# HVSchematic.net
KiCad netlist of a schematic drawn in Altium Designer
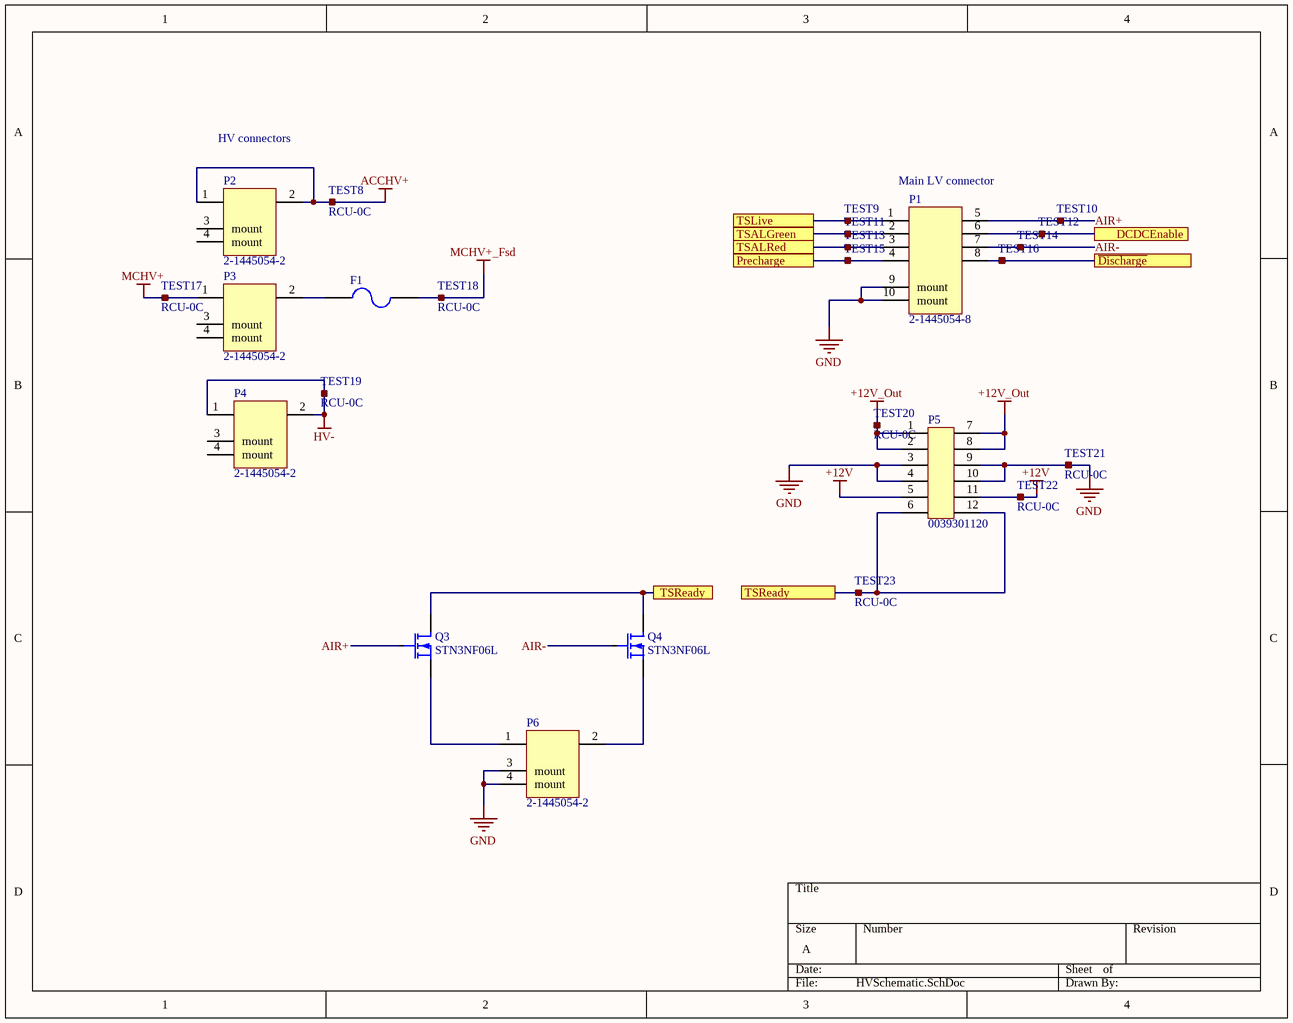
[diagram p0: HVSchematic.SchDoc]

(export (version "E")
  (design (tool "Eeschema 10.0.6"))
  (components
    (comp (ref "F1")
      (value "~")
      (footprint "0885004.DR")
      (fields (field (name "MFRPARTNO") "0885004.DR") (field (name "CREATED_BY") "Graydon"))
      (libsource (lib "Altium-Lib") (part "Fuse"))
    )
    (comp (ref "P1")
      (value "2-1445054-8")
      (footprint "2-1445054-8")
      (description "1x8 connector")
      (fields (field (name "CREATED_BY") "Graydon"))
      (libsource (lib "Altium-Lib") (part "2-1445054-8"))
    )
    (comp (ref "P2")
      (value "2-1445054-2")
      (footprint "2-1445054-2")
      (description "1x2 connector")
      (fields (field (name "CREATED_BY") "Graydon") (field (name "UPDATED_BY") "Null"))
      (libsource (lib "Altium-Lib") (part "2-1445054-2"))
    )
    (comp (ref "P3")
      (value "2-1445054-2")
      (footprint "2-1445054-2")
      (description "1x2 connector")
      (fields (field (name "CREATED_BY") "Graydon") (field (name "UPDATED_BY") "Null"))
      (libsource (lib "Altium-Lib") (part "2-1445054-2"))
    )
    (comp (ref "P4")
      (value "2-1445054-2")
      (footprint "2-1445054-2")
      (description "1x2 connector")
      (fields (field (name "CREATED_BY") "Graydon") (field (name "UPDATED_BY") "Null"))
      (libsource (lib "Altium-Lib") (part "2-1445054-2"))
    )
    (comp (ref "P5")
      (value "0039301120")
      (footprint "0039301120")
      (description "Molex Minifit Jr 12p right angle")
      (libsource (lib "Altium-Lib") (part "0039301120"))
    )
    (comp (ref "P6")
      (value "2-1445054-2")
      (footprint "2-1445054-2")
      (description "1x2 connector")
      (fields (field (name "CREATED_BY") "Graydon") (field (name "UPDATED_BY") "Null"))
      (libsource (lib "Altium-Lib") (part "2-1445054-2"))
    )
    (comp (ref "Q3")
      (value "STN3NF06L")
      (footprint "STN3NF06L")
      (description "MOSFET N-CH 60V 4A SOT223")
      (fields (field (name "CREATED_BY") "Graydon"))
      (libsource (lib "Altium-Lib") (part "STN3NF06L"))
    )
    (comp (ref "Q4")
      (value "STN3NF06L")
      (footprint "STN3NF06L")
      (description "MOSFET N-CH 60V 4A SOT223")
      (fields (field (name "CREATED_BY") "Graydon"))
      (libsource (lib "Altium-Lib") (part "STN3NF06L"))
    )
    (comp (ref "TEST8")
      (value "RCU-0C")
      (footprint "RCU-0C")
      (description "Test point")
      (fields (field (name "CREATED_BY") "Graydon") (field (name "UPDATED_BY") "Null"))
      (libsource (lib "Altium-Lib") (part "RCU-0C"))
    )
    (comp (ref "TEST9")
      (value "RCU-0C")
      (footprint "RCU-0C")
      (description "Test point")
      (fields (field (name "CREATED_BY") "Graydon") (field (name "UPDATED_BY") "Null"))
      (libsource (lib "Altium-Lib") (part "RCU-0C"))
    )
    (comp (ref "TEST10")
      (value "RCU-0C")
      (footprint "RCU-0C")
      (description "Test point")
      (fields (field (name "CREATED_BY") "Graydon") (field (name "UPDATED_BY") "Null"))
      (libsource (lib "Altium-Lib") (part "RCU-0C"))
    )
    (comp (ref "TEST11")
      (value "RCU-0C")
      (footprint "RCU-0C")
      (description "Test point")
      (fields (field (name "CREATED_BY") "Graydon") (field (name "UPDATED_BY") "Null"))
      (libsource (lib "Altium-Lib") (part "RCU-0C"))
    )
    (comp (ref "TEST12")
      (value "RCU-0C")
      (footprint "RCU-0C")
      (description "Test point")
      (fields (field (name "CREATED_BY") "Graydon") (field (name "UPDATED_BY") "Null"))
      (libsource (lib "Altium-Lib") (part "RCU-0C"))
    )
    (comp (ref "TEST13")
      (value "RCU-0C")
      (footprint "RCU-0C")
      (description "Test point")
      (fields (field (name "CREATED_BY") "Graydon") (field (name "UPDATED_BY") "Null"))
      (libsource (lib "Altium-Lib") (part "RCU-0C"))
    )
    (comp (ref "TEST14")
      (value "RCU-0C")
      (footprint "RCU-0C")
      (description "Test point")
      (fields (field (name "CREATED_BY") "Graydon") (field (name "UPDATED_BY") "Null"))
      (libsource (lib "Altium-Lib") (part "RCU-0C"))
    )
    (comp (ref "TEST15")
      (value "RCU-0C")
      (footprint "RCU-0C")
      (description "Test point")
      (fields (field (name "CREATED_BY") "Graydon") (field (name "UPDATED_BY") "Null"))
      (libsource (lib "Altium-Lib") (part "RCU-0C"))
    )
    (comp (ref "TEST16")
      (value "RCU-0C")
      (footprint "RCU-0C")
      (description "Test point")
      (fields (field (name "CREATED_BY") "Graydon") (field (name "UPDATED_BY") "Null"))
      (libsource (lib "Altium-Lib") (part "RCU-0C"))
    )
    (comp (ref "TEST17")
      (value "RCU-0C")
      (footprint "RCU-0C")
      (description "Test point")
      (fields (field (name "CREATED_BY") "Graydon") (field (name "UPDATED_BY") "Null"))
      (libsource (lib "Altium-Lib") (part "RCU-0C"))
    )
    (comp (ref "TEST18")
      (value "RCU-0C")
      (footprint "RCU-0C")
      (description "Test point")
      (fields (field (name "CREATED_BY") "Graydon") (field (name "UPDATED_BY") "Null"))
      (libsource (lib "Altium-Lib") (part "RCU-0C"))
    )
    (comp (ref "TEST19")
      (value "RCU-0C")
      (footprint "RCU-0C")
      (description "Test point")
      (fields (field (name "CREATED_BY") "Graydon") (field (name "UPDATED_BY") "Null"))
      (libsource (lib "Altium-Lib") (part "RCU-0C"))
    )
    (comp (ref "TEST20")
      (value "RCU-0C")
      (footprint "RCU-0C")
      (description "Test point")
      (fields (field (name "CREATED_BY") "Graydon") (field (name "UPDATED_BY") "Null"))
      (libsource (lib "Altium-Lib") (part "RCU-0C"))
    )
    (comp (ref "TEST21")
      (value "RCU-0C")
      (footprint "RCU-0C")
      (description "Test point")
      (fields (field (name "CREATED_BY") "Graydon") (field (name "UPDATED_BY") "Null"))
      (libsource (lib "Altium-Lib") (part "RCU-0C"))
    )
    (comp (ref "TEST22")
      (value "RCU-0C")
      (footprint "RCU-0C")
      (description "Test point")
      (fields (field (name "CREATED_BY") "Graydon") (field (name "UPDATED_BY") "Null"))
      (libsource (lib "Altium-Lib") (part "RCU-0C"))
    )
    (comp (ref "TEST23")
      (value "RCU-0C")
      (footprint "RCU-0C")
      (description "Test point")
      (fields (field (name "CREATED_BY") "Graydon") (field (name "UPDATED_BY") "Null"))
      (libsource (lib "Altium-Lib") (part "RCU-0C"))
    )
  )
  (nets
    (net (code "1") (name "+12V") (class "Default")
      (node (ref "P5") (pin "11") (pintype "power_in"))
      (node (ref "P5") (pin "5") (pintype "power_in"))
      (node (ref "TEST22") (pin "1") (pintype "passive"))
    )
    (net (code "2") (name "+12V_Out") (class "Default")
      (node (ref "P5") (pin "1") (pintype "power_in"))
      (node (ref "P5") (pin "2") (pintype "power_in"))
      (node (ref "P5") (pin "7") (pintype "power_in"))
      (node (ref "P5") (pin "8") (pintype "power_in"))
      (node (ref "TEST20") (pin "1") (pintype "passive"))
    )
    (net (code "3") (name "/AIR+") (class "Default")
      (node (ref "P1") (pin "5") (pintype "power_in"))
      (node (ref "Q3") (pin "1") (pinfunction "G_1") (pintype "passive"))
      (node (ref "TEST10") (pin "1") (pintype "passive"))
    )
    (net (code "4") (name "/AIR-") (class "Default")
      (node (ref "P1") (pin "7") (pintype "power_in"))
      (node (ref "Q4") (pin "1") (pinfunction "G_1") (pintype "passive"))
      (node (ref "TEST14") (pin "1") (pintype "passive"))
    )
    (net (code "5") (name "/DCDCEnable") (class "Default")
      (node (ref "P1") (pin "6") (pintype "power_in"))
      (node (ref "TEST12") (pin "1") (pintype "passive"))
    )
    (net (code "6") (name "/Discharge") (class "Default")
      (node (ref "P1") (pin "8") (pintype "power_in"))
      (node (ref "TEST16") (pin "1") (pintype "passive"))
    )
    (net (code "7") (name "/Precharge") (class "Default")
      (node (ref "P1") (pin "4") (pintype "power_in"))
      (node (ref "TEST15") (pin "1") (pintype "passive"))
    )
    (net (code "8") (name "/TSALGreen") (class "Default")
      (node (ref "P1") (pin "2") (pintype "power_in"))
      (node (ref "TEST11") (pin "1") (pintype "passive"))
    )
    (net (code "9") (name "/TSALRed") (class "Default")
      (node (ref "P1") (pin "3") (pintype "power_in"))
      (node (ref "TEST13") (pin "1") (pintype "passive"))
    )
    (net (code "10") (name "/TSLive") (class "Default")
      (node (ref "P1") (pin "1") (pintype "power_in"))
      (node (ref "TEST9") (pin "1") (pintype "passive"))
    )
    (net (code "11") (name "/TSReady") (class "Default")
      (node (ref "P5") (pin "12") (pintype "power_in"))
      (node (ref "P5") (pin "6") (pintype "power_in"))
      (node (ref "Q3") (pin "2") (pinfunction "D_2") (pintype "passive"))
      (node (ref "Q4") (pin "2") (pinfunction "D_2") (pintype "passive"))
      (node (ref "TEST23") (pin "1") (pintype "passive"))
    )
    (net (code "12") (name "ACCHV+") (class "Default")
      (node (ref "P2") (pin "1") (pintype "power_in"))
      (node (ref "P2") (pin "2") (pintype "power_in"))
      (node (ref "TEST8") (pin "1") (pintype "passive"))
    )
    (net (code "13") (name "GND") (class "Default")
      (node (ref "P1") (pin "10") (pinfunction "mount_10") (pintype "power_in"))
      (node (ref "P1") (pin "9") (pinfunction "mount_9") (pintype "power_in"))
      (node (ref "P5") (pin "10") (pintype "power_in"))
      (node (ref "P5") (pin "3") (pintype "power_in"))
      (node (ref "P5") (pin "4") (pintype "power_in"))
      (node (ref "P5") (pin "9") (pintype "power_in"))
      (node (ref "P6") (pin "3") (pinfunction "mount_3") (pintype "power_in"))
      (node (ref "P6") (pin "4") (pinfunction "mount_4") (pintype "power_in"))
      (node (ref "TEST21") (pin "1") (pintype "passive"))
    )
    (net (code "14") (name "HV-") (class "Default")
      (node (ref "P4") (pin "1") (pintype "power_in"))
      (node (ref "P4") (pin "2") (pintype "power_in"))
      (node (ref "TEST19") (pin "1") (pintype "passive"))
    )
    (net (code "15") (name "MCHV+") (class "Default")
      (node (ref "P3") (pin "1") (pintype "power_in"))
      (node (ref "TEST17") (pin "1") (pintype "passive"))
    )
    (net (code "16") (name "MCHV+_Fsd") (class "Default")
      (node (ref "F1") (pin "2") (pinfunction "2_2") (pintype "passive"))
      (node (ref "TEST18") (pin "1") (pintype "passive"))
    )
    (net (code "17") (name "Net-(F1-Pad1)") (class "Default")
      (node (ref "F1") (pin "1") (pinfunction "1_1") (pintype "passive"))
      (node (ref "P3") (pin "2") (pintype "power_in"))
    )
    (net (code "18") (name "Net-(Q3-S)") (class "Default")
      (node (ref "P6") (pin "1") (pintype "power_in"))
      (node (ref "Q3") (pin "3") (pinfunction "S_3") (pintype "passive"))
    )
    (net (code "19") (name "Net-(Q4-S)") (class "Default")
      (node (ref "P6") (pin "2") (pintype "power_in"))
      (node (ref "Q4") (pin "3") (pinfunction "S_3") (pintype "passive"))
    )
    (net (code "20") (name "unconnected-(P2-mount-Pad3)") (class "Default")
      (node (ref "P2") (pin "3") (pinfunction "mount_3") (pintype "power_in"))
    )
    (net (code "21") (name "unconnected-(P2-mount-Pad4)") (class "Default")
      (node (ref "P2") (pin "4") (pinfunction "mount_4") (pintype "power_in"))
    )
    (net (code "22") (name "unconnected-(P3-mount-Pad3)") (class "Default")
      (node (ref "P3") (pin "3") (pinfunction "mount_3") (pintype "power_in"))
    )
    (net (code "23") (name "unconnected-(P3-mount-Pad4)") (class "Default")
      (node (ref "P3") (pin "4") (pinfunction "mount_4") (pintype "power_in"))
    )
    (net (code "24") (name "unconnected-(P4-mount-Pad3)") (class "Default")
      (node (ref "P4") (pin "3") (pinfunction "mount_3") (pintype "power_in"))
    )
    (net (code "25") (name "unconnected-(P4-mount-Pad4)") (class "Default")
      (node (ref "P4") (pin "4") (pinfunction "mount_4") (pintype "power_in"))
    )
  )
)
